# 04_ZYNQ_BANK13_33_34.net
KiCad netlist of a schematic drawn in Altium Designer
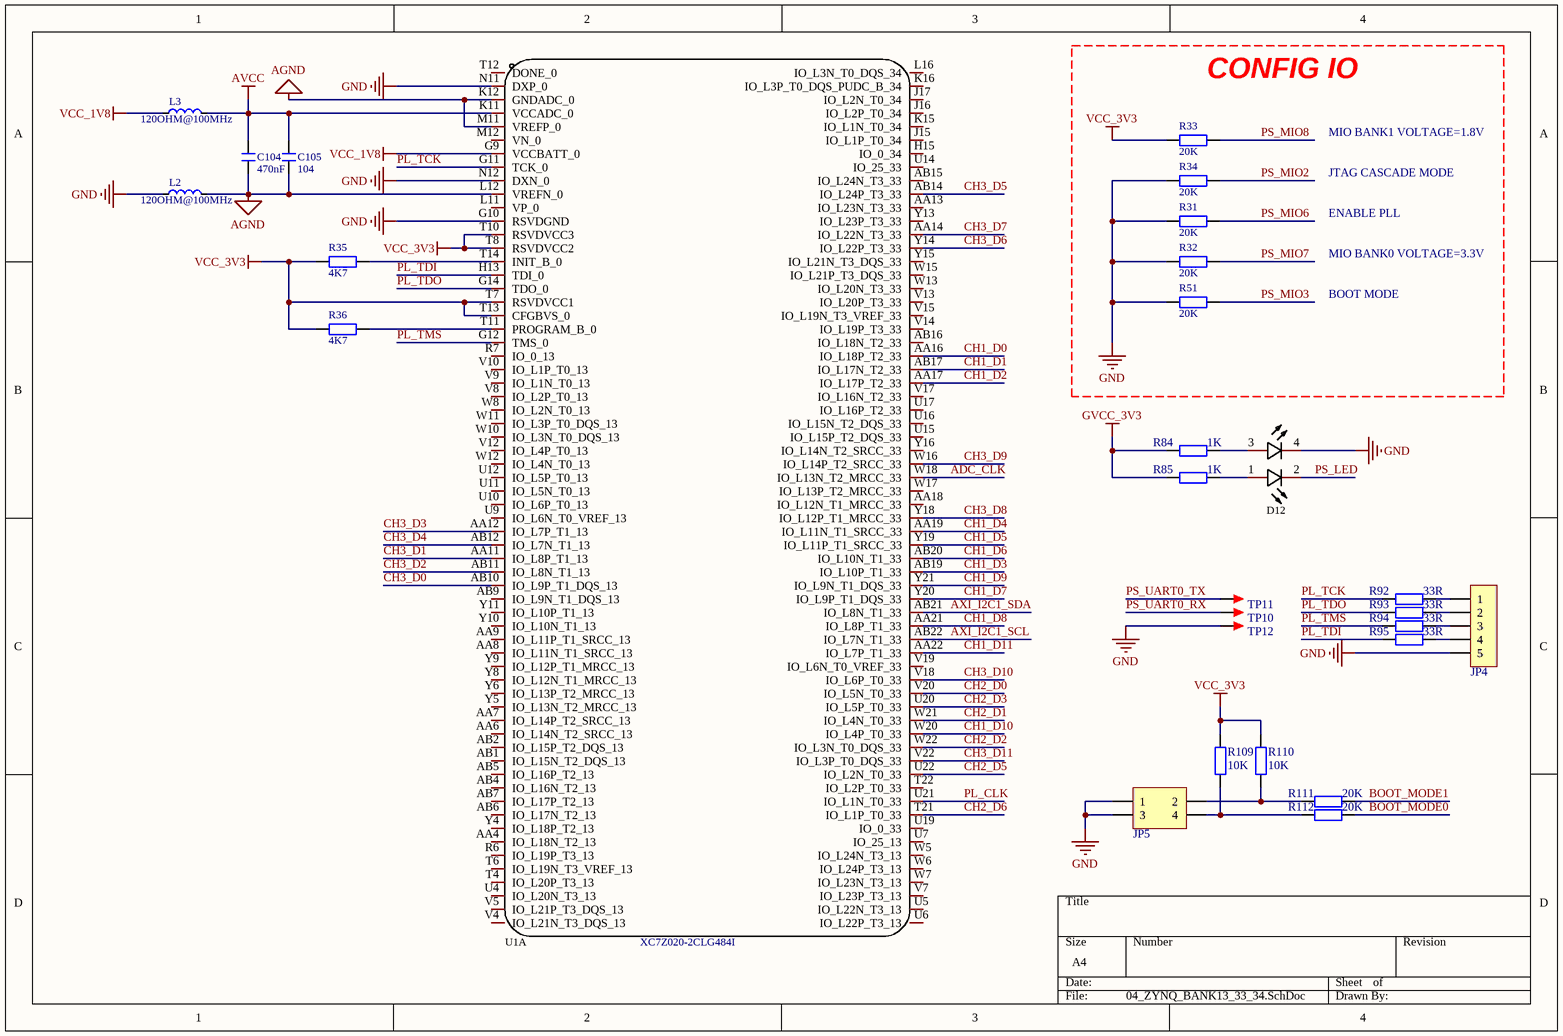
[diagram p0: 04_ZYNQ_BANK13_33_34.SchDoc]

(export (version "E")
  (design (tool "Eeschema 10.0.6"))
  (components
    (comp (ref "C104")
      (value "470nF")
      (footprint "C 0402")
      (description "无极性贴片电容")
      (fields (field (name "版权归属") "源创客"))
      (libsource (lib "STM32MP157核心板封装库V1.2") (part "C"))
    )
    (comp (ref "C105")
      (value "104")
      (footprint "C 0402")
      (description "无极性贴片电容")
      (fields (field (name "版权归属") "源创客"))
      (libsource (lib "STM32MP157核心板封装库V1.2") (part "C"))
    )
    (comp (ref "D12")
      (value "A694B/2SYG/S530-E2")
      (footprint "Dual-LED")
      (fields (field (name "MANUFACTURER") "EVERLIGHT(亿光)"))
      (libsource (lib "Dual-LED") (part "A694B/2SYG/S530-E2"))
    )
    (comp (ref "JP4")
      (value "HDR-1X5")
      (footprint "XH2.54-LI-5P")
      (description "5P接插件")
      (fields (field (name "版权归属") "源创客"))
      (libsource (lib "4.5   - 接插件-脚距2.54") (part "Header 5"))
    )
    (comp (ref "JP5")
      (value "Header2X2")
      (footprint "HDR2.54-LI-2x2P")
      (description "2*2P接插件")
      (fields (field (name "版权归属") "源创客"))
      (libsource (lib "4.5   - 接插件-脚距2.54") (part "Header 2X2"))
    )
    (comp (ref "L2")
      (value "120OHM@100MHz")
      (footprint "L 0603")
      (description "小功率贴片电感磁珠")
      (fields (field (name "版权归属") "源创客"))
      (libsource (lib "STM32MP157核心板封装库V1.2") (part "L"))
    )
    (comp (ref "L3")
      (value "120OHM@100MHz")
      (footprint "L 0603")
      (description "小功率贴片电感磁珠")
      (fields (field (name "版权归属") "源创客"))
      (libsource (lib "STM32MP157核心板封装库V1.2") (part "L"))
    )
    (comp (ref "R31")
      (value "20K")
      (footprint "R 0402")
      (description "贴片电阻")
      (fields (field (name "版权归属") "源创客"))
      (libsource (lib "STM32MP157核心板封装库V1.2") (part "R"))
    )
    (comp (ref "R32")
      (value "20K")
      (footprint "R 0402")
      (description "贴片电阻")
      (fields (field (name "版权归属") "源创客"))
      (libsource (lib "STM32MP157核心板封装库V1.2") (part "R"))
    )
    (comp (ref "R33")
      (value "20K")
      (footprint "R 0402")
      (description "贴片电阻")
      (fields (field (name "版权归属") "源创客"))
      (libsource (lib "STM32MP157核心板封装库V1.2") (part "R"))
    )
    (comp (ref "R34")
      (value "20K")
      (footprint "R 0402")
      (description "贴片电阻")
      (fields (field (name "版权归属") "源创客"))
      (libsource (lib "STM32MP157核心板封装库V1.2") (part "R"))
    )
    (comp (ref "R35")
      (value "4K7")
      (footprint "R 0402")
      (description "贴片电阻")
      (fields (field (name "版权归属") "源创客"))
      (libsource (lib "STM32MP157核心板封装库V1.2") (part "R"))
    )
    (comp (ref "R36")
      (value "4K7")
      (footprint "R 0402")
      (description "贴片电阻")
      (fields (field (name "版权归属") "源创客"))
      (libsource (lib "STM32MP157核心板封装库V1.2") (part "R"))
    )
    (comp (ref "R51")
      (value "20K")
      (footprint "R 0402")
      (description "贴片电阻")
      (fields (field (name "版权归属") "源创客"))
      (libsource (lib "STM32MP157核心板封装库V1.2") (part "R"))
    )
    (comp (ref "R84")
      (value "1K")
      (footprint "R 0603")
      (description "贴片电阻")
      (fields (field (name "版权归属") "源创客"))
      (libsource (lib "STM32MP15x底板封装库V1.4") (part "R"))
    )
    (comp (ref "R85")
      (value "1K")
      (footprint "R 0603")
      (description "贴片电阻")
      (fields (field (name "版权归属") "源创客"))
      (libsource (lib "STM32MP15x底板封装库V1.4") (part "R"))
    )
    (comp (ref "R92")
      (value "33R")
      (footprint "R 0603")
      (description "贴片电阻")
      (fields (field (name "版权归属") "源创客"))
      (libsource (lib "STM32MP15x底板封装库V1.4") (part "R"))
    )
    (comp (ref "R93")
      (value "33R")
      (footprint "R 0603")
      (description "贴片电阻")
      (fields (field (name "版权归属") "源创客"))
      (libsource (lib "STM32MP15x底板封装库V1.4") (part "R"))
    )
    (comp (ref "R94")
      (value "33R")
      (footprint "R 0603")
      (description "贴片电阻")
      (fields (field (name "版权归属") "源创客"))
      (libsource (lib "STM32MP15x底板封装库V1.4") (part "R"))
    )
    (comp (ref "R95")
      (value "33R")
      (footprint "R 0603")
      (description "贴片电阻")
      (fields (field (name "版权归属") "源创客"))
      (libsource (lib "STM32MP15x底板封装库V1.4") (part "R"))
    )
    (comp (ref "R109")
      (value "10K")
      (footprint "R 0603")
      (description "贴片电阻")
      (fields (field (name "版权归属") "源创客"))
      (libsource (lib "STM32MP15x底板封装库V1.4") (part "R"))
    )
    (comp (ref "R110")
      (value "10K")
      (footprint "R 0603")
      (description "贴片电阻")
      (fields (field (name "版权归属") "源创客"))
      (libsource (lib "STM32MP15x底板封装库V1.4") (part "R"))
    )
    (comp (ref "R111")
      (value "20K")
      (footprint "R 0603")
      (description "贴片电阻")
      (fields (field (name "版权归属") "源创客"))
      (libsource (lib "STM32MP15x底板封装库V1.4") (part "R"))
    )
    (comp (ref "R112")
      (value "20K")
      (footprint "R 0603")
      (description "贴片电阻")
      (fields (field (name "版权归属") "源创客"))
      (libsource (lib "STM32MP15x底板封装库V1.4") (part "R"))
    )
    (comp (ref "TP10")
      (value "TEST")
      (footprint "TEST 1")
      (description "测试点")
      (fields (field (name "版权归属") "源创客"))
      (libsource (lib "15.1 - 未分类器件") (part "TEST"))
    )
    (comp (ref "TP11")
      (value "TEST")
      (footprint "TEST 1")
      (description "测试点")
      (fields (field (name "版权归属") "源创客"))
      (libsource (lib "15.1 - 未分类器件") (part "TEST"))
    )
    (comp (ref "TP12")
      (value "TEST")
      (footprint "TEST 1")
      (description "测试点")
      (fields (field (name "版权归属") "源创客"))
      (libsource (lib "15.1 - 未分类器件") (part "TEST"))
    )
    (comp (ref "U1")
      (value "XC7Z020-2CLG484I")
      (footprint "FPBGA-484_L19.0-W19.0-R22-C22-P0.80-BL")
      (fields (field (name "MANUFACTURER") "XILINX(赛灵思)"))
      (libsource (lib "XC7Z020-2CLG484I1") (part "XC7Z020-2CLG484I"))
    )
  )
  (nets
    (net (code "1") (name "/ADC_CLK") (class "Default")
      (node (ref "U1") (pin "W18") (pinfunction "IO_L13N_T2_MRCC_33_W18") (pintype "passive"))
    )
    (net (code "2") (name "/AXI_I2C1_SCL") (class "Default")
      (node (ref "U1") (pin "AB22") (pinfunction "IO_L7N_T1_33_AB22") (pintype "passive"))
    )
    (net (code "3") (name "/AXI_I2C1_SDA") (class "Default")
      (node (ref "U1") (pin "AB21") (pinfunction "IO_L8N_T1_33_AB21") (pintype "passive"))
    )
    (net (code "4") (name "/BOOT_MODE0") (class "Default")
      (node (ref "R112") (pin "1") (pinfunction "1_1") (pintype "passive"))
    )
    (net (code "5") (name "/BOOT_MODE1") (class "Default")
      (node (ref "R111") (pin "1") (pinfunction "1_1") (pintype "passive"))
    )
    (net (code "6") (name "/CH1_D0") (class "Default")
      (node (ref "U1") (pin "AA16") (pinfunction "IO_L18P_T2_33_AA16") (pintype "passive"))
    )
    (net (code "7") (name "/CH1_D1") (class "Default")
      (node (ref "U1") (pin "AB17") (pinfunction "IO_L17N_T2_33_AB17") (pintype "passive"))
    )
    (net (code "8") (name "/CH1_D2") (class "Default")
      (node (ref "U1") (pin "AA17") (pinfunction "IO_L17P_T2_33_AA17") (pintype "passive"))
    )
    (net (code "9") (name "/CH1_D3") (class "Default")
      (node (ref "U1") (pin "AB19") (pinfunction "IO_L10P_T1_33_AB19") (pintype "passive"))
    )
    (net (code "10") (name "/CH1_D4") (class "Default")
      (node (ref "U1") (pin "AA19") (pinfunction "IO_L11N_T1_SRCC_33_AA19") (pintype "passive"))
    )
    (net (code "11") (name "/CH1_D5") (class "Default")
      (node (ref "U1") (pin "Y19") (pinfunction "IO_L11P_T1_SRCC_33_Y19") (pintype "passive"))
    )
    (net (code "12") (name "/CH1_D6") (class "Default")
      (node (ref "U1") (pin "AB20") (pinfunction "IO_L10N_T1_33_AB20") (pintype "passive"))
    )
    (net (code "13") (name "/CH1_D7") (class "Default")
      (node (ref "U1") (pin "Y20") (pinfunction "IO_L9P_T1_DQS_33_Y20") (pintype "passive"))
    )
    (net (code "14") (name "/CH1_D8") (class "Default")
      (node (ref "U1") (pin "AA21") (pinfunction "IO_L8P_T1_33_AA21") (pintype "passive"))
    )
    (net (code "15") (name "/CH1_D9") (class "Default")
      (node (ref "U1") (pin "Y21") (pinfunction "IO_L9N_T1_DQS_33_Y21") (pintype "passive"))
    )
    (net (code "16") (name "/CH1_D10") (class "Default")
      (node (ref "U1") (pin "W20") (pinfunction "IO_L4P_T0_33_W20") (pintype "passive"))
    )
    (net (code "17") (name "/CH1_D11") (class "Default")
      (node (ref "U1") (pin "AA22") (pinfunction "IO_L7P_T1_33_AA22") (pintype "passive"))
    )
    (net (code "18") (name "/CH2_D0") (class "Default")
      (node (ref "U1") (pin "V20") (pinfunction "IO_L5N_T0_33_V20") (pintype "passive"))
    )
    (net (code "19") (name "/CH2_D1") (class "Default")
      (node (ref "U1") (pin "W21") (pinfunction "IO_L4N_T0_33_W21") (pintype "passive"))
    )
    (net (code "20") (name "/CH2_D2") (class "Default")
      (node (ref "U1") (pin "W22") (pinfunction "IO_L3N_T0_DQS_33_W22") (pintype "passive"))
    )
    (net (code "21") (name "/CH2_D3") (class "Default")
      (node (ref "U1") (pin "U20") (pinfunction "IO_L5P_T0_33_U20") (pintype "passive"))
    )
    (net (code "22") (name "/CH2_D5") (class "Default")
      (node (ref "U1") (pin "U22") (pinfunction "IO_L2N_T0_33_U22") (pintype "passive"))
    )
    (net (code "23") (name "/CH2_D6") (class "Default")
      (node (ref "U1") (pin "T21") (pinfunction "IO_L1P_T0_33_T21") (pintype "passive"))
    )
    (net (code "24") (name "/CH3_D0") (class "Default")
      (node (ref "U1") (pin "AB10") (pinfunction "IO_L9P_T1_DQS_13_AB10") (pintype "passive"))
    )
    (net (code "25") (name "/CH3_D1") (class "Default")
      (node (ref "U1") (pin "AA11") (pinfunction "IO_L8P_T1_13_AA11") (pintype "passive"))
    )
    (net (code "26") (name "/CH3_D2") (class "Default")
      (node (ref "U1") (pin "AB11") (pinfunction "IO_L8N_T1_13_AB11") (pintype "passive"))
    )
    (net (code "27") (name "/CH3_D3") (class "Default")
      (node (ref "U1") (pin "AA12") (pinfunction "IO_L7P_T1_13_AA12") (pintype "passive"))
    )
    (net (code "28") (name "/CH3_D4") (class "Default")
      (node (ref "U1") (pin "AB12") (pinfunction "IO_L7N_T1_13_AB12") (pintype "passive"))
    )
    (net (code "29") (name "/CH3_D5") (class "Default")
      (node (ref "U1") (pin "AB14") (pinfunction "IO_L24P_T3_33_AB14") (pintype "passive"))
    )
    (net (code "30") (name "/CH3_D6") (class "Default")
      (node (ref "U1") (pin "Y14") (pinfunction "IO_L22P_T3_33_Y14") (pintype "passive"))
    )
    (net (code "31") (name "/CH3_D7") (class "Default")
      (node (ref "U1") (pin "AA14") (pinfunction "IO_L22N_T3_33_AA14") (pintype "passive"))
    )
    (net (code "32") (name "/CH3_D8") (class "Default")
      (node (ref "U1") (pin "Y18") (pinfunction "IO_L12P_T1_MRCC_33_Y18") (pintype "passive"))
    )
    (net (code "33") (name "/CH3_D9") (class "Default")
      (node (ref "U1") (pin "W16") (pinfunction "IO_L14P_T2_SRCC_33_W16") (pintype "passive"))
    )
    (net (code "34") (name "/CH3_D10") (class "Default")
      (node (ref "U1") (pin "V18") (pinfunction "IO_L6P_T0_33_V18") (pintype "passive"))
    )
    (net (code "35") (name "/CH3_D11") (class "Default")
      (node (ref "U1") (pin "V22") (pinfunction "IO_L3P_T0_DQS_33_V22") (pintype "passive"))
    )
    (net (code "36") (name "/PL_CLK") (class "Default")
      (node (ref "U1") (pin "U21") (pinfunction "IO_L1N_T0_33_U21") (pintype "passive"))
    )
    (net (code "37") (name "/PL_TCK") (class "Default")
      (node (ref "R92") (pin "1") (pinfunction "1_1") (pintype "passive"))
      (node (ref "U1") (pin "G11") (pinfunction "TCK_0_G11") (pintype "passive"))
    )
    (net (code "38") (name "/PL_TDI") (class "Default")
      (node (ref "R95") (pin "1") (pinfunction "1_1") (pintype "passive"))
      (node (ref "U1") (pin "H13") (pinfunction "TDI_0_H13") (pintype "passive"))
    )
    (net (code "39") (name "/PL_TDO") (class "Default")
      (node (ref "R93") (pin "1") (pinfunction "1_1") (pintype "passive"))
      (node (ref "U1") (pin "G14") (pinfunction "TDO_0_G14") (pintype "passive"))
    )
    (net (code "40") (name "/PL_TMS") (class "Default")
      (node (ref "R94") (pin "1") (pinfunction "1_1") (pintype "passive"))
      (node (ref "U1") (pin "G12") (pinfunction "TMS_0_G12") (pintype "passive"))
    )
    (net (code "41") (name "/PS_LED") (class "Default")
      (node (ref "D12") (pin "2") (pinfunction "K1_2") (pintype "passive"))
    )
    (net (code "42") (name "/PS_MIO2") (class "Default")
      (node (ref "R34") (pin "2") (pinfunction "2_2") (pintype "passive"))
    )
    (net (code "43") (name "/PS_MIO3") (class "Default")
      (node (ref "R51") (pin "2") (pinfunction "2_2") (pintype "passive"))
    )
    (net (code "44") (name "/PS_MIO6") (class "Default")
      (node (ref "R31") (pin "2") (pinfunction "2_2") (pintype "passive"))
    )
    (net (code "45") (name "/PS_MIO7") (class "Default")
      (node (ref "R32") (pin "2") (pinfunction "2_2") (pintype "passive"))
    )
    (net (code "46") (name "/PS_MIO8") (class "Default")
      (node (ref "R33") (pin "2") (pinfunction "2_2") (pintype "passive"))
    )
    (net (code "47") (name "/PS_UART0_RX") (class "Default")
      (node (ref "TP10") (pin "1") (pinfunction "1_1") (pintype "passive"))
    )
    (net (code "48") (name "/PS_UART0_TX") (class "Default")
      (node (ref "TP11") (pin "1") (pinfunction "1_1") (pintype "passive"))
    )
    (net (code "49") (name "AGND") (class "Default")
      (node (ref "C104") (pin "1") (pinfunction "1_1") (pintype "passive"))
      (node (ref "C105") (pin "1") (pinfunction "1_1") (pintype "passive"))
      (node (ref "L2") (pin "2") (pinfunction "2_2") (pintype "passive"))
      (node (ref "U1") (pin "K12") (pinfunction "GNDADC_0_K12") (pintype "passive"))
      (node (ref "U1") (pin "L12") (pinfunction "VREFN_0_L12") (pintype "passive"))
      (node (ref "U1") (pin "M11") (pinfunction "VREFP_0_M11") (pintype "passive"))
    )
    (net (code "50") (name "AVCC") (class "Default")
      (node (ref "C104") (pin "2") (pinfunction "2_2") (pintype "passive"))
      (node (ref "C105") (pin "2") (pinfunction "2_2") (pintype "passive"))
      (node (ref "L3") (pin "2") (pinfunction "2_2") (pintype "passive"))
      (node (ref "U1") (pin "K11") (pinfunction "VCCADC_0_K11") (pintype "passive"))
    )
    (net (code "51") (name "GND") (class "Default")
      (node (ref "D12") (pin "4") (pinfunction "K2_4") (pintype "passive"))
      (node (ref "JP4") (pin "5") (pinfunction "5_5") (pintype "passive"))
      (node (ref "JP5") (pin "1") (pinfunction "1_1") (pintype "passive"))
      (node (ref "JP5") (pin "3") (pinfunction "3_3") (pintype "passive"))
      (node (ref "L2") (pin "1") (pinfunction "1_1") (pintype "passive"))
      (node (ref "R31") (pin "1") (pinfunction "1_1") (pintype "passive"))
      (node (ref "R32") (pin "1") (pinfunction "1_1") (pintype "passive"))
      (node (ref "R34") (pin "1") (pinfunction "1_1") (pintype "passive"))
      (node (ref "R51") (pin "1") (pinfunction "1_1") (pintype "passive"))
      (node (ref "TP12") (pin "1") (pinfunction "1_1") (pintype "passive"))
      (node (ref "U1") (pin "G10") (pinfunction "RSVDGND_G10") (pintype "passive"))
      (node (ref "U1") (pin "N11") (pinfunction "DXP_0_N11") (pintype "passive"))
      (node (ref "U1") (pin "N12") (pinfunction "DXN_0_N12") (pintype "passive"))
    )
    (net (code "52") (name "GVCC_3V3") (class "Default")
      (node (ref "R84") (pin "1") (pinfunction "1_1") (pintype "passive"))
      (node (ref "R85") (pin "1") (pinfunction "1_1") (pintype "passive"))
    )
    (net (code "53") (name "Net-(D12-A1)") (class "Default")
      (node (ref "D12") (pin "1") (pinfunction "A1_1") (pintype "passive"))
      (node (ref "R85") (pin "2") (pinfunction "2_2") (pintype "passive"))
    )
    (net (code "54") (name "Net-(D12-A2)") (class "Default")
      (node (ref "D12") (pin "3") (pinfunction "A2_3") (pintype "passive"))
      (node (ref "R84") (pin "2") (pinfunction "2_2") (pintype "passive"))
    )
    (net (code "55") (name "Net-(JP4-Pad1)") (class "Default")
      (node (ref "JP4") (pin "1") (pinfunction "1_1") (pintype "passive"))
      (node (ref "R92") (pin "2") (pinfunction "2_2") (pintype "passive"))
    )
    (net (code "56") (name "Net-(JP4-Pad2)") (class "Default")
      (node (ref "JP4") (pin "2") (pinfunction "2_2") (pintype "passive"))
      (node (ref "R93") (pin "2") (pinfunction "2_2") (pintype "passive"))
    )
    (net (code "57") (name "Net-(JP4-Pad3)") (class "Default")
      (node (ref "JP4") (pin "3") (pinfunction "3_3") (pintype "passive"))
      (node (ref "R94") (pin "2") (pinfunction "2_2") (pintype "passive"))
    )
    (net (code "58") (name "Net-(JP4-Pad4)") (class "Default")
      (node (ref "JP4") (pin "4") (pinfunction "4_4") (pintype "passive"))
      (node (ref "R95") (pin "2") (pinfunction "2_2") (pintype "passive"))
    )
    (net (code "59") (name "Net-(JP5-Pad2)") (class "Default")
      (node (ref "JP5") (pin "2") (pinfunction "2_2") (pintype "passive"))
      (node (ref "R110") (pin "2") (pinfunction "2_2") (pintype "passive"))
      (node (ref "R111") (pin "2") (pinfunction "2_2") (pintype "passive"))
    )
    (net (code "60") (name "Net-(JP5-Pad4)") (class "Default")
      (node (ref "JP5") (pin "4") (pinfunction "4_4") (pintype "passive"))
      (node (ref "R109") (pin "2") (pinfunction "2_2") (pintype "passive"))
      (node (ref "R112") (pin "2") (pinfunction "2_2") (pintype "passive"))
    )
    (net (code "61") (name "Net-(U1A-INIT_B_0)") (class "Default")
      (node (ref "R35") (pin "2") (pinfunction "2_2") (pintype "passive"))
      (node (ref "U1") (pin "T14") (pinfunction "INIT_B_0_T14") (pintype "passive"))
    )
    (net (code "62") (name "Net-(U1A-PROGRAM_B_0)") (class "Default")
      (node (ref "R36") (pin "2") (pinfunction "2_2") (pintype "passive"))
      (node (ref "U1") (pin "T11") (pinfunction "PROGRAM_B_0_T11") (pintype "passive"))
    )
    (net (code "63") (name "VCC_1V8") (class "Default")
      (node (ref "L3") (pin "1") (pinfunction "1_1") (pintype "passive"))
      (node (ref "U1") (pin "G9") (pinfunction "VCCBATT_0_G9") (pintype "passive"))
    )
    (net (code "64") (name "VCC_3V3") (class "Default")
      (node (ref "R109") (pin "1") (pinfunction "1_1") (pintype "passive"))
      (node (ref "R110") (pin "1") (pinfunction "1_1") (pintype "passive"))
      (node (ref "R33") (pin "1") (pinfunction "1_1") (pintype "passive"))
      (node (ref "R35") (pin "1") (pinfunction "1_1") (pintype "passive"))
      (node (ref "R36") (pin "1") (pinfunction "1_1") (pintype "passive"))
      (node (ref "U1") (pin "T10") (pinfunction "RSVDVCC3_T10") (pintype "passive"))
      (node (ref "U1") (pin "T13") (pinfunction "CFGBVS_0_T13") (pintype "passive"))
      (node (ref "U1") (pin "T7") (pinfunction "RSVDVCC1_T7") (pintype "passive"))
      (node (ref "U1") (pin "T8") (pinfunction "RSVDVCC2_T8") (pintype "passive"))
    )
    (net (code "65") (name "unconnected-(U1A-DONE_0-PadT12)") (class "Default")
      (node (ref "U1") (pin "T12") (pinfunction "DONE_0_T12") (pintype "passive"))
    )
    (net (code "66") (name "unconnected-(U1A-IO_0_13-PadR7)") (class "Default")
      (node (ref "U1") (pin "R7") (pinfunction "IO_0_13_R7") (pintype "passive"))
    )
    (net (code "67") (name "unconnected-(U1A-IO_0_33-PadU19)") (class "Default")
      (node (ref "U1") (pin "U19") (pinfunction "IO_0_33_U19") (pintype "passive"))
    )
    (net (code "68") (name "unconnected-(U1A-IO_0_34-PadH15)") (class "Default")
      (node (ref "U1") (pin "H15") (pinfunction "IO_0_34_H15") (pintype "passive"))
    )
    (net (code "69") (name "unconnected-(U1A-IO_25_13-PadU7)") (class "Default")
      (node (ref "U1") (pin "U7") (pinfunction "IO_25_13_U7") (pintype "passive"))
    )
    (net (code "70") (name "unconnected-(U1A-IO_25_33-PadU14)") (class "Default")
      (node (ref "U1") (pin "U14") (pinfunction "IO_25_33_U14") (pintype "passive"))
    )
    (net (code "71") (name "unconnected-(U1A-IO_L1N_T0_13-PadV9)") (class "Default")
      (node (ref "U1") (pin "V9") (pinfunction "IO_L1N_T0_13_V9") (pintype "passive"))
    )
    (net (code "72") (name "unconnected-(U1A-IO_L1N_T0_34-PadK15)") (class "Default")
      (node (ref "U1") (pin "K15") (pinfunction "IO_L1N_T0_34_K15") (pintype "passive"))
    )
    (net (code "73") (name "unconnected-(U1A-IO_L1P_T0_13-PadV10)") (class "Default")
      (node (ref "U1") (pin "V10") (pinfunction "IO_L1P_T0_13_V10") (pintype "passive"))
    )
    (net (code "74") (name "unconnected-(U1A-IO_L1P_T0_34-PadJ15)") (class "Default")
      (node (ref "U1") (pin "J15") (pinfunction "IO_L1P_T0_34_J15") (pintype "passive"))
    )
    (net (code "75") (name "unconnected-(U1A-IO_L2N_T0_13-PadW8)") (class "Default")
      (node (ref "U1") (pin "W8") (pinfunction "IO_L2N_T0_13_W8") (pintype "passive"))
    )
    (net (code "76") (name "unconnected-(U1A-IO_L2N_T0_34-PadJ17)") (class "Default")
      (node (ref "U1") (pin "J17") (pinfunction "IO_L2N_T0_34_J17") (pintype "passive"))
    )
    (net (code "77") (name "unconnected-(U1A-IO_L2P_T0_13-PadV8)") (class "Default")
      (node (ref "U1") (pin "V8") (pinfunction "IO_L2P_T0_13_V8") (pintype "passive"))
    )
    (net (code "78") (name "unconnected-(U1A-IO_L2P_T0_33-PadT22)") (class "Default")
      (node (ref "U1") (pin "T22") (pinfunction "IO_L2P_T0_33_T22") (pintype "passive"))
    )
    (net (code "79") (name "unconnected-(U1A-IO_L2P_T0_34-PadJ16)") (class "Default")
      (node (ref "U1") (pin "J16") (pinfunction "IO_L2P_T0_34_J16") (pintype "passive"))
    )
    (net (code "80") (name "unconnected-(U1A-IO_L3N_T0_DQS_13-PadW10)") (class "Default")
      (node (ref "U1") (pin "W10") (pinfunction "IO_L3N_T0_DQS_13_W10") (pintype "passive"))
    )
    (net (code "81") (name "unconnected-(U1A-IO_L3N_T0_DQS_34-PadL16)") (class "Default")
      (node (ref "U1") (pin "L16") (pinfunction "IO_L3N_T0_DQS_34_L16") (pintype "passive"))
    )
    (net (code "82") (name "unconnected-(U1A-IO_L3P_T0_DQS_13-PadW11)") (class "Default")
      (node (ref "U1") (pin "W11") (pinfunction "IO_L3P_T0_DQS_13_W11") (pintype "passive"))
    )
    (net (code "83") (name "unconnected-(U1A-IO_L3P_T0_DQS_PUDC_B_34-PadK16)") (class "Default")
      (node (ref "U1") (pin "K16") (pinfunction "IO_L3P_T0_DQS_PUDC_B_34_K16") (pintype "passive"))
    )
    (net (code "84") (name "unconnected-(U1A-IO_L4N_T0_13-PadW12)") (class "Default")
      (node (ref "U1") (pin "W12") (pinfunction "IO_L4N_T0_13_W12") (pintype "passive"))
    )
    (net (code "85") (name "unconnected-(U1A-IO_L4P_T0_13-PadV12)") (class "Default")
      (node (ref "U1") (pin "V12") (pinfunction "IO_L4P_T0_13_V12") (pintype "passive"))
    )
    (net (code "86") (name "unconnected-(U1A-IO_L5N_T0_13-PadU11)") (class "Default")
      (node (ref "U1") (pin "U11") (pinfunction "IO_L5N_T0_13_U11") (pintype "passive"))
    )
    (net (code "87") (name "unconnected-(U1A-IO_L5P_T0_13-PadU12)") (class "Default")
      (node (ref "U1") (pin "U12") (pinfunction "IO_L5P_T0_13_U12") (pintype "passive"))
    )
    (net (code "88") (name "unconnected-(U1A-IO_L6N_T0_VREF_13-PadU9)") (class "Default")
      (node (ref "U1") (pin "U9") (pinfunction "IO_L6N_T0_VREF_13_U9") (pintype "passive"))
    )
    (net (code "89") (name "unconnected-(U1A-IO_L6N_T0_VREF_33-PadV19)") (class "Default")
      (node (ref "U1") (pin "V19") (pinfunction "IO_L6N_T0_VREF_33_V19") (pintype "passive"))
    )
    (net (code "90") (name "unconnected-(U1A-IO_L6P_T0_13-PadU10)") (class "Default")
      (node (ref "U1") (pin "U10") (pinfunction "IO_L6P_T0_13_U10") (pintype "passive"))
    )
    (net (code "91") (name "unconnected-(U1A-IO_L9N_T1_DQS_13-PadAB9)") (class "Default")
      (node (ref "U1") (pin "AB9") (pinfunction "IO_L9N_T1_DQS_13_AB9") (pintype "passive"))
    )
    (net (code "92") (name "unconnected-(U1A-IO_L10N_T1_13-PadY10)") (class "Default")
      (node (ref "U1") (pin "Y10") (pinfunction "IO_L10N_T1_13_Y10") (pintype "passive"))
    )
    (net (code "93") (name "unconnected-(U1A-IO_L10P_T1_13-PadY11)") (class "Default")
      (node (ref "U1") (pin "Y11") (pinfunction "IO_L10P_T1_13_Y11") (pintype "passive"))
    )
    (net (code "94") (name "unconnected-(U1A-IO_L11N_T1_SRCC_13-PadAA8)") (class "Default")
      (node (ref "U1") (pin "AA8") (pinfunction "IO_L11N_T1_SRCC_13_AA8") (pintype "passive"))
    )
    (net (code "95") (name "unconnected-(U1A-IO_L11P_T1_SRCC_13-PadAA9)") (class "Default")
      (node (ref "U1") (pin "AA9") (pinfunction "IO_L11P_T1_SRCC_13_AA9") (pintype "passive"))
    )
    (net (code "96") (name "unconnected-(U1A-IO_L12N_T1_MRCC_13-PadY8)") (class "Default")
      (node (ref "U1") (pin "Y8") (pinfunction "IO_L12N_T1_MRCC_13_Y8") (pintype "passive"))
    )
    (net (code "97") (name "unconnected-(U1A-IO_L12N_T1_MRCC_33-PadAA18)") (class "Default")
      (node (ref "U1") (pin "AA18") (pinfunction "IO_L12N_T1_MRCC_33_AA18") (pintype "passive"))
    )
    (net (code "98") (name "unconnected-(U1A-IO_L12P_T1_MRCC_13-PadY9)") (class "Default")
      (node (ref "U1") (pin "Y9") (pinfunction "IO_L12P_T1_MRCC_13_Y9") (pintype "passive"))
    )
    (net (code "99") (name "unconnected-(U1A-IO_L13N_T2_MRCC_13-PadY5)") (class "Default")
      (node (ref "U1") (pin "Y5") (pinfunction "IO_L13N_T2_MRCC_13_Y5") (pintype "passive"))
    )
    (net (code "100") (name "unconnected-(U1A-IO_L13P_T2_MRCC_13-PadY6)") (class "Default")
      (node (ref "U1") (pin "Y6") (pinfunction "IO_L13P_T2_MRCC_13_Y6") (pintype "passive"))
    )
    (net (code "101") (name "unconnected-(U1A-IO_L13P_T2_MRCC_33-PadW17)") (class "Default")
      (node (ref "U1") (pin "W17") (pinfunction "IO_L13P_T2_MRCC_33_W17") (pintype "passive"))
    )
    (net (code "102") (name "unconnected-(U1A-IO_L14N_T2_SRCC_13-PadAA6)") (class "Default")
      (node (ref "U1") (pin "AA6") (pinfunction "IO_L14N_T2_SRCC_13_AA6") (pintype "passive"))
    )
    (net (code "103") (name "unconnected-(U1A-IO_L14N_T2_SRCC_33-PadY16)") (class "Default")
      (node (ref "U1") (pin "Y16") (pinfunction "IO_L14N_T2_SRCC_33_Y16") (pintype "passive"))
    )
    (net (code "104") (name "unconnected-(U1A-IO_L14P_T2_SRCC_13-PadAA7)") (class "Default")
      (node (ref "U1") (pin "AA7") (pinfunction "IO_L14P_T2_SRCC_13_AA7") (pintype "passive"))
    )
    (net (code "105") (name "unconnected-(U1A-IO_L15N_T2_DQS_13-PadAB1)") (class "Default")
      (node (ref "U1") (pin "AB1") (pinfunction "IO_L15N_T2_DQS_13_AB1") (pintype "passive"))
    )
    (net (code "106") (name "unconnected-(U1A-IO_L15N_T2_DQS_33-PadU16)") (class "Default")
      (node (ref "U1") (pin "U16") (pinfunction "IO_L15N_T2_DQS_33_U16") (pintype "passive"))
    )
    (net (code "107") (name "unconnected-(U1A-IO_L15P_T2_DQS_13-PadAB2)") (class "Default")
      (node (ref "U1") (pin "AB2") (pinfunction "IO_L15P_T2_DQS_13_AB2") (pintype "passive"))
    )
    (net (code "108") (name "unconnected-(U1A-IO_L15P_T2_DQS_33-PadU15)") (class "Default")
      (node (ref "U1") (pin "U15") (pinfunction "IO_L15P_T2_DQS_33_U15") (pintype "passive"))
    )
    (net (code "109") (name "unconnected-(U1A-IO_L16N_T2_13-PadAB4)") (class "Default")
      (node (ref "U1") (pin "AB4") (pinfunction "IO_L16N_T2_13_AB4") (pintype "passive"))
    )
    (net (code "110") (name "unconnected-(U1A-IO_L16N_T2_33-PadV17)") (class "Default")
      (node (ref "U1") (pin "V17") (pinfunction "IO_L16N_T2_33_V17") (pintype "passive"))
    )
    (net (code "111") (name "unconnected-(U1A-IO_L16P_T2_13-PadAB5)") (class "Default")
      (node (ref "U1") (pin "AB5") (pinfunction "IO_L16P_T2_13_AB5") (pintype "passive"))
    )
    (net (code "112") (name "unconnected-(U1A-IO_L16P_T2_33-PadU17)") (class "Default")
      (node (ref "U1") (pin "U17") (pinfunction "IO_L16P_T2_33_U17") (pintype "passive"))
    )
    (net (code "113") (name "unconnected-(U1A-IO_L17N_T2_13-PadAB6)") (class "Default")
      (node (ref "U1") (pin "AB6") (pinfunction "IO_L17N_T2_13_AB6") (pintype "passive"))
    )
    (net (code "114") (name "unconnected-(U1A-IO_L17P_T2_13-PadAB7)") (class "Default")
      (node (ref "U1") (pin "AB7") (pinfunction "IO_L17P_T2_13_AB7") (pintype "passive"))
    )
    (net (code "115") (name "unconnected-(U1A-IO_L18N_T2_13-PadAA4)") (class "Default")
      (node (ref "U1") (pin "AA4") (pinfunction "IO_L18N_T2_13_AA4") (pintype "passive"))
    )
    (net (code "116") (name "unconnected-(U1A-IO_L18N_T2_33-PadAB16)") (class "Default")
      (node (ref "U1") (pin "AB16") (pinfunction "IO_L18N_T2_33_AB16") (pintype "passive"))
    )
    (net (code "117") (name "unconnected-(U1A-IO_L18P_T2_13-PadY4)") (class "Default")
      (node (ref "U1") (pin "Y4") (pinfunction "IO_L18P_T2_13_Y4") (pintype "passive"))
    )
    (net (code "118") (name "unconnected-(U1A-IO_L19N_T3_VREF_13-PadT6)") (class "Default")
      (node (ref "U1") (pin "T6") (pinfunction "IO_L19N_T3_VREF_13_T6") (pintype "passive"))
    )
    (net (code "119") (name "unconnected-(U1A-IO_L19N_T3_VREF_33-PadV15)") (class "Default")
      (node (ref "U1") (pin "V15") (pinfunction "IO_L19N_T3_VREF_33_V15") (pintype "passive"))
    )
    (net (code "120") (name "unconnected-(U1A-IO_L19P_T3_13-PadR6)") (class "Default")
      (node (ref "U1") (pin "R6") (pinfunction "IO_L19P_T3_13_R6") (pintype "passive"))
    )
    (net (code "121") (name "unconnected-(U1A-IO_L19P_T3_33-PadV14)") (class "Default")
      (node (ref "U1") (pin "V14") (pinfunction "IO_L19P_T3_33_V14") (pintype "passive"))
    )
    (net (code "122") (name "unconnected-(U1A-IO_L20N_T3_13-PadU4)") (class "Default")
      (node (ref "U1") (pin "U4") (pinfunction "IO_L20N_T3_13_U4") (pintype "passive"))
    )
    (net (code "123") (name "unconnected-(U1A-IO_L20N_T3_33-PadW13)") (class "Default")
      (node (ref "U1") (pin "W13") (pinfunction "IO_L20N_T3_33_W13") (pintype "passive"))
    )
    (net (code "124") (name "unconnected-(U1A-IO_L20P_T3_13-PadT4)") (class "Default")
      (node (ref "U1") (pin "T4") (pinfunction "IO_L20P_T3_13_T4") (pintype "passive"))
    )
    (net (code "125") (name "unconnected-(U1A-IO_L20P_T3_33-PadV13)") (class "Default")
      (node (ref "U1") (pin "V13") (pinfunction "IO_L20P_T3_33_V13") (pintype "passive"))
    )
    (net (code "126") (name "unconnected-(U1A-IO_L21N_T3_DQS_13-PadV4)") (class "Default")
      (node (ref "U1") (pin "V4") (pinfunction "IO_L21N_T3_DQS_13_V4") (pintype "passive"))
    )
    (net (code "127") (name "unconnected-(U1A-IO_L21N_T3_DQS_33-PadY15)") (class "Default")
      (node (ref "U1") (pin "Y15") (pinfunction "IO_L21N_T3_DQS_33_Y15") (pintype "passive"))
    )
    (net (code "128") (name "unconnected-(U1A-IO_L21P_T3_DQS_13-PadV5)") (class "Default")
      (node (ref "U1") (pin "V5") (pinfunction "IO_L21P_T3_DQS_13_V5") (pintype "passive"))
    )
    (net (code "129") (name "unconnected-(U1A-IO_L21P_T3_DQS_33-PadW15)") (class "Default")
      (node (ref "U1") (pin "W15") (pinfunction "IO_L21P_T3_DQS_33_W15") (pintype "passive"))
    )
    (net (code "130") (name "unconnected-(U1A-IO_L22N_T3_13-PadU5)") (class "Default")
      (node (ref "U1") (pin "U5") (pinfunction "IO_L22N_T3_13_U5") (pintype "passive"))
    )
    (net (code "131") (name "unconnected-(U1A-IO_L22P_T3_13-PadU6)") (class "Default")
      (node (ref "U1") (pin "U6") (pinfunction "IO_L22P_T3_13_U6") (pintype "passive"))
    )
    (net (code "132") (name "unconnected-(U1A-IO_L23N_T3_13-PadW7)") (class "Default")
      (node (ref "U1") (pin "W7") (pinfunction "IO_L23N_T3_13_W7") (pintype "passive"))
    )
    (net (code "133") (name "unconnected-(U1A-IO_L23N_T3_33-PadAA13)") (class "Default")
      (node (ref "U1") (pin "AA13") (pinfunction "IO_L23N_T3_33_AA13") (pintype "passive"))
    )
    (net (code "134") (name "unconnected-(U1A-IO_L23P_T3_13-PadV7)") (class "Default")
      (node (ref "U1") (pin "V7") (pinfunction "IO_L23P_T3_13_V7") (pintype "passive"))
    )
    (net (code "135") (name "unconnected-(U1A-IO_L23P_T3_33-PadY13)") (class "Default")
      (node (ref "U1") (pin "Y13") (pinfunction "IO_L23P_T3_33_Y13") (pintype "passive"))
    )
    (net (code "136") (name "unconnected-(U1A-IO_L24N_T3_13-PadW5)") (class "Default")
      (node (ref "U1") (pin "W5") (pinfunction "IO_L24N_T3_13_W5") (pintype "passive"))
    )
    (net (code "137") (name "unconnected-(U1A-IO_L24N_T3_33-PadAB15)") (class "Default")
      (node (ref "U1") (pin "AB15") (pinfunction "IO_L24N_T3_33_AB15") (pintype "passive"))
    )
    (net (code "138") (name "unconnected-(U1A-IO_L24P_T3_13-PadW6)") (class "Default")
      (node (ref "U1") (pin "W6") (pinfunction "IO_L24P_T3_13_W6") (pintype "passive"))
    )
    (net (code "139") (name "unconnected-(U1A-VN_0-PadM12)") (class "Default")
      (node (ref "U1") (pin "M12") (pinfunction "VN_0_M12") (pintype "passive"))
    )
    (net (code "140") (name "unconnected-(U1A-VP_0-PadL11)") (class "Default")
      (node (ref "U1") (pin "L11") (pinfunction "VP_0_L11") (pintype "passive"))
    )
  )
)
